# CAS_4.net
KiCad netlist of a schematic drawn in Altium Designer
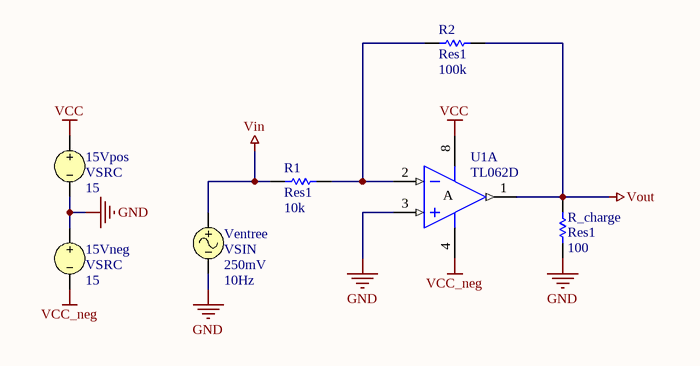
[diagram p0: CAS_4.SchDoc]

(export (version "E")
  (design (tool "Eeschema 10.0.6"))
  (components
    (comp (ref "15Vneg")
      (value "VSRC")
      (description "Voltage Source")
      (fields (field (name "ALTIUM_VALUE") "15") (field (name "PUBLISHER") "Altium Limited"))
      (libsource (lib "Simulation Generic Components") (part "VSRC"))
    )
    (comp (ref "15Vpos")
      (value "VSRC")
      (description "Voltage Source")
      (fields (field (name "ALTIUM_VALUE") "15") (field (name "PUBLISHER") "Altium Limited"))
      (libsource (lib "Simulation Generic Components") (part "VSRC"))
    )
    (comp (ref "R1")
      (value "Res1")
      (footprint "AXIAL-0.3")
      (description "Resistor")
      (fields (field (name "ALTIUM_VALUE") "10k") (field (name "PUBLISHER") "Altium Limited"))
      (libsource (lib "Miscellaneous Devices") (part "Res1"))
    )
    (comp (ref "R2")
      (value "Res1")
      (footprint "AXIAL-0.3")
      (description "Resistor")
      (fields (field (name "ALTIUM_VALUE") "100k") (field (name "PUBLISHER") "Altium Limited"))
      (libsource (lib "Miscellaneous Devices") (part "Res1"))
    )
    (comp (ref "R_charge")
      (value "Res1")
      (footprint "AXIAL-0.3")
      (description "Resistor")
      (fields (field (name "ALTIUM_VALUE") "100") (field (name "PUBLISHER") "Altium Limited"))
      (libsource (lib "Miscellaneous Devices") (part "Res1"))
    )
    (comp (ref "U1")
      (value "TL062D")
      (footprint "D008_L")
      (description "Low-Power JFET-Input Operational Amplifier")
      (fields (field (name "PUBLISHER") "Altium Limited"))
      (libsource (lib "TI Operational Amplifier") (part "TL062D"))
    )
    (comp (ref "Ventree")
      (value "VSIN")
      (description "Sinusoidal Voltage Source")
      (fields
        (field (name "AMPLITUDE") "250mV")
        (field (name "FREQUENCY") "10Hz")
        (field (name "PUBLISHER") "Altium Limited")
      )
      (libsource (lib "Simulation Sources") (part "VSIN"))
    )
  )
  (nets
    (net (code "1") (name "GND") (class "Default")
      (node (ref "15Vneg") (pin "1") (pinfunction "1_1") (pintype "passive"))
      (node (ref "15Vpos") (pin "2") (pinfunction "2_2") (pintype "passive"))
      (node (ref "R_charge") (pin "1") (pinfunction "1_1") (pintype "passive"))
      (node (ref "U1") (pin "3") (pinfunction "IN+_3") (pintype "input"))
      (node (ref "Ventree") (pin "2") (pinfunction "2_2") (pintype "passive"))
    )
    (net (code "2") (name "Net-(U1A-IN-)") (class "Default")
      (node (ref "R1") (pin "2") (pinfunction "2_2") (pintype "passive"))
      (node (ref "R2") (pin "1") (pinfunction "1_1") (pintype "passive"))
      (node (ref "U1") (pin "2") (pinfunction "IN-_2") (pintype "input"))
    )
    (net (code "3") (name "VCC") (class "Default")
      (node (ref "15Vpos") (pin "1") (pinfunction "1_1") (pintype "passive"))
      (node (ref "U1") (pin "8") (pinfunction "V+_8") (pintype "power_in"))
    )
    (net (code "4") (name "VCC_neg") (class "Default")
      (node (ref "15Vneg") (pin "2") (pinfunction "2_2") (pintype "passive"))
      (node (ref "U1") (pin "4") (pinfunction "V-_4") (pintype "power_in"))
    )
    (net (code "5") (name "Vin") (class "Default")
      (node (ref "R1") (pin "1") (pinfunction "1_1") (pintype "passive"))
      (node (ref "Ventree") (pin "1") (pinfunction "1_1") (pintype "passive"))
    )
    (net (code "6") (name "Vout") (class "Default")
      (node (ref "R2") (pin "2") (pinfunction "2_2") (pintype "passive"))
      (node (ref "R_charge") (pin "2") (pinfunction "2_2") (pintype "passive"))
      (node (ref "U1") (pin "1") (pinfunction "OUT_1") (pintype "output"))
    )
  )
)
